# LINDIY.net
KiCad netlist of a schematic drawn in Altium Designer
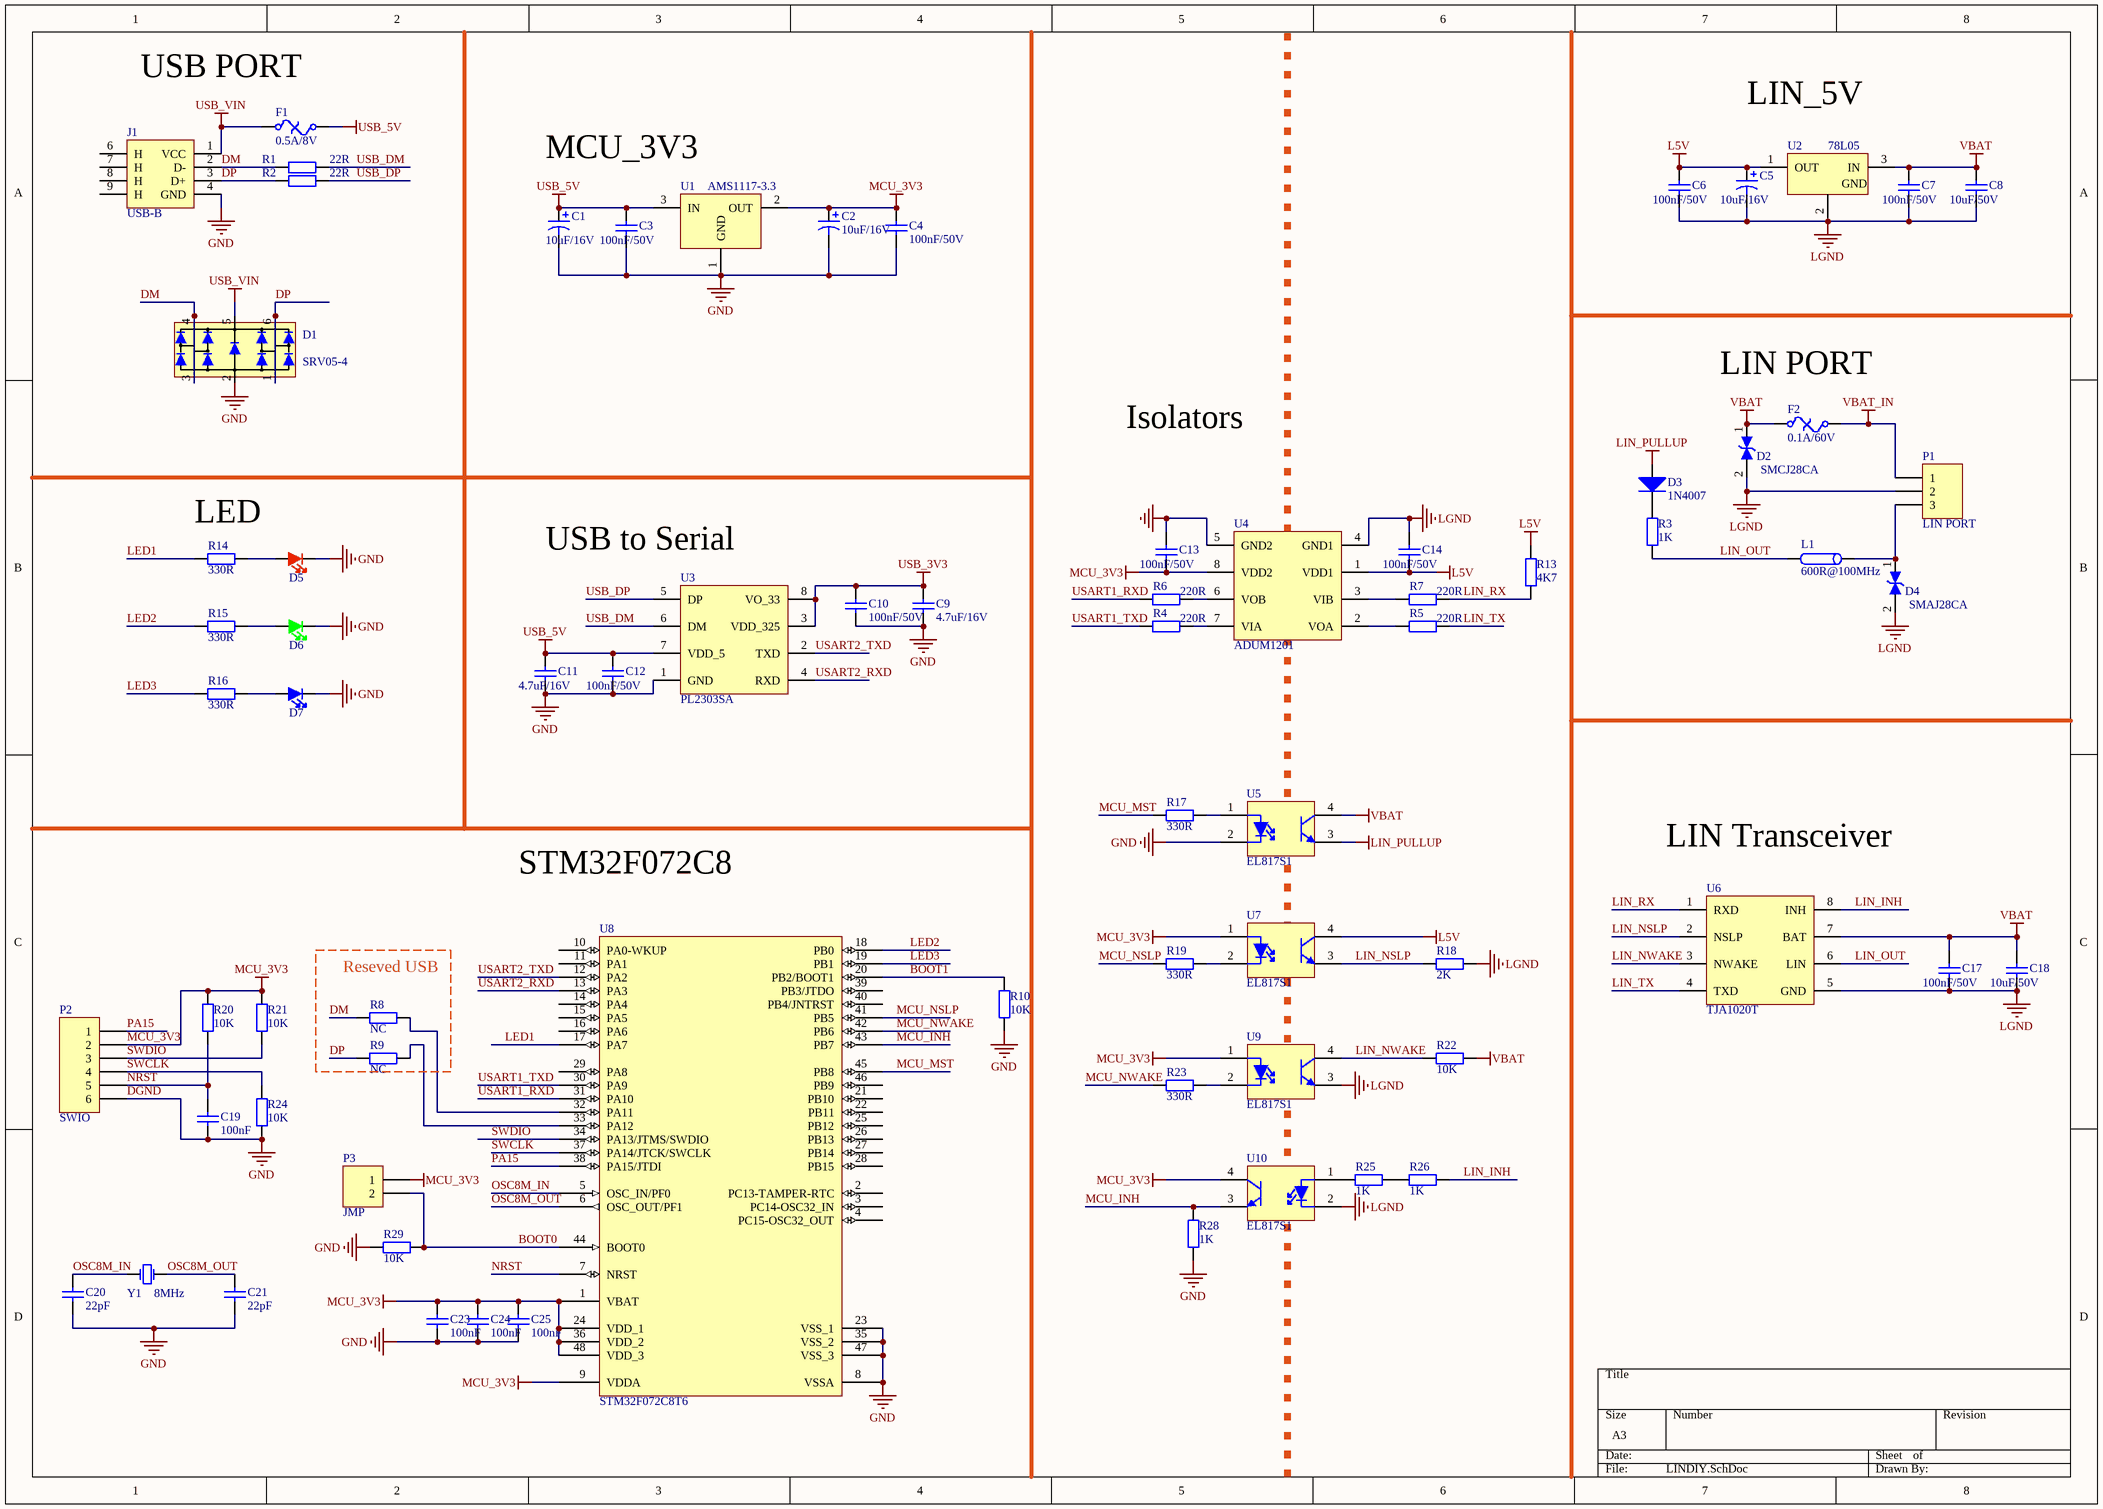
[diagram p0: LINDIY.SchDoc]

(export (version "E")
  (design (tool "Eeschema 10.0.6"))
  (components
    (comp (ref "C1")
      (value "10uF/16V")
      (footprint "LC-CASE-A_3216")
      (description "Polarized Capacitor (Axial)")
      (fields (field (name "PUBLISHER") "Altium Limited"))
      (libsource (lib "usrSchLib") (part "Cap Pol2"))
    )
    (comp (ref "C2")
      (value "10uF/16V")
      (footprint "LC-CASE-A_3216")
      (description "Polarized Capacitor (Axial)")
      (fields (field (name "PUBLISHER") "Altium Limited"))
      (libsource (lib "usrSchLib") (part "Cap Pol2"))
    )
    (comp (ref "C3")
      (value "100nF/50V")
      (footprint "LC-0603_C")
      (description "Capacitor")
      (fields (field (name "PUBLISHER") "Altium Limited"))
      (libsource (lib "usrSchLib") (part "Cap"))
    )
    (comp (ref "C4")
      (value "100nF/50V")
      (footprint "LC-0603_C")
      (description "Capacitor")
      (fields (field (name "PUBLISHER") "Altium Limited"))
      (libsource (lib "usrSchLib") (part "Cap"))
    )
    (comp (ref "C5")
      (value "10uF/16V")
      (footprint "LC-CASE-A_3216")
      (description "Polarized Capacitor (Axial)")
      (fields (field (name "PUBLISHER") "Altium Limited"))
      (libsource (lib "usrSchLib") (part "Cap Pol2"))
    )
    (comp (ref "C6")
      (value "100nF/50V")
      (footprint "LC-0603_C")
      (description "Capacitor")
      (fields (field (name "PUBLISHER") "Altium Limited"))
      (libsource (lib "usrSchLib") (part "Cap"))
    )
    (comp (ref "C7")
      (value "100nF/50V")
      (footprint "LC-0603_C")
      (description "Capacitor")
      (fields (field (name "PUBLISHER") "Altium Limited"))
      (libsource (lib "usrSchLib") (part "Cap"))
    )
    (comp (ref "C8")
      (value "10uF/50V")
      (footprint "LC-1206_C")
      (description "Capacitor")
      (fields (field (name "PUBLISHER") "Altium Limited"))
      (libsource (lib "usrSchLib") (part "Cap"))
    )
    (comp (ref "C9")
      (value "4.7uF/16V")
      (footprint "LC-0603_C")
      (description "Capacitor")
      (fields (field (name "PUBLISHER") "Altium Limited"))
      (libsource (lib "usrSchLib") (part "Cap"))
    )
    (comp (ref "C10")
      (value "100nF/50V")
      (footprint "LC-0603_C")
      (description "Capacitor")
      (fields (field (name "PUBLISHER") "Altium Limited"))
      (libsource (lib "usrSchLib") (part "Cap"))
    )
    (comp (ref "C11")
      (value "4.7uF/16V")
      (footprint "LC-0603_C")
      (description "Capacitor")
      (fields (field (name "PUBLISHER") "Altium Limited"))
      (libsource (lib "usrSchLib") (part "Cap"))
    )
    (comp (ref "C12")
      (value "100nF/50V")
      (footprint "LC-0603_C")
      (description "Capacitor")
      (fields (field (name "PUBLISHER") "Altium Limited"))
      (libsource (lib "usrSchLib") (part "Cap"))
    )
    (comp (ref "C13")
      (value "100nF/50V")
      (footprint "LC-0603_C")
      (description "Capacitor")
      (fields (field (name "PUBLISHER") "Altium Limited"))
      (libsource (lib "usrSchLib") (part "Cap"))
    )
    (comp (ref "C14")
      (value "100nF/50V")
      (footprint "LC-0603_C")
      (description "Capacitor")
      (fields (field (name "PUBLISHER") "Altium Limited"))
      (libsource (lib "usrSchLib") (part "Cap"))
    )
    (comp (ref "C17")
      (value "100nF/50V")
      (footprint "LC-0603_C")
      (description "Capacitor")
      (fields (field (name "PUBLISHER") "Altium Limited"))
      (libsource (lib "usrSchLib") (part "Cap"))
    )
    (comp (ref "C18")
      (value "10uF/50V")
      (footprint "LC-1206_C")
      (description "Capacitor")
      (fields (field (name "PUBLISHER") "Altium Limited"))
      (libsource (lib "usrSchLib") (part "Cap"))
    )
    (comp (ref "C19")
      (value "100nF")
      (footprint "LC-0603_C")
      (description "Capacitor")
      (fields (field (name "PUBLISHER") "Altium Limited"))
      (libsource (lib "usrSchLib") (part "Cap"))
    )
    (comp (ref "C20")
      (value "22pF")
      (footprint "LC-0603_C")
      (description "Capacitor")
      (fields (field (name "PUBLISHER") "Altium Limited"))
      (libsource (lib "usrSchLib") (part "Cap"))
    )
    (comp (ref "C21")
      (value "22pF")
      (footprint "LC-0603_C")
      (description "Capacitor")
      (fields (field (name "PUBLISHER") "Altium Limited"))
      (libsource (lib "usrSchLib") (part "Cap"))
    )
    (comp (ref "C23")
      (value "100nF")
      (footprint "LC-0603_C")
      (description "Capacitor")
      (fields (field (name "PUBLISHER") "Altium Limited"))
      (libsource (lib "usrSchLib") (part "Cap"))
    )
    (comp (ref "C24")
      (value "100nF")
      (footprint "LC-0603_C")
      (description "Capacitor")
      (fields (field (name "PUBLISHER") "Altium Limited"))
      (libsource (lib "usrSchLib") (part "Cap"))
    )
    (comp (ref "C25")
      (value "100nF")
      (footprint "LC-0603_C")
      (description "Capacitor")
      (fields (field (name "PUBLISHER") "Altium Limited"))
      (libsource (lib "usrSchLib") (part "Cap"))
    )
    (comp (ref "D1")
      (value "SRV05-4")
      (footprint "LC-SOT-23-6")
      (description "Low Capacitance TVS Diode Array")
      (libsource (lib "usrSchLib") (part "SRV05-4"))
    )
    (comp (ref "D2")
      (value "SMCJ28CA")
      (footprint "LC-SMC(DO-214AB)_S1")
      (description "Zener Diode")
      (libsource (lib "usrSchLib") (part "P6KE6.8CA"))
    )
    (comp (ref "D3")
      (value "1N4007")
      (footprint "LC-SMA(DO-214AC)_S1")
      (description "Silicon Low Leakage Diode")
      (fields (field (name "PUBLISHER") "Altium Limited"))
      (libsource (lib "usrSchLib") (part "Diode BAS116"))
    )
    (comp (ref "D4")
      (value "SMAJ28CA")
      (footprint "LC-SMA(DO-214AC)_S1")
      (description "Zener Diode")
      (libsource (lib "usrSchLib") (part "P6KE6.8CA"))
    )
    (comp (ref "D5")
      (value "LED_RED")
      (footprint "LC-0805_LED_S1")
      (libsource (lib "usrSchLib") (part "LED-R"))
    )
    (comp (ref "D6")
      (value "LED_GREEG")
      (footprint "LC-0805_LED_S1")
      (libsource (lib "usrSchLib") (part "LED-G"))
    )
    (comp (ref "D7")
      (value "LED_RED")
      (footprint "LC-0805_LED_S1")
      (libsource (lib "usrSchLib") (part "LED-B"))
    )
    (comp (ref "F1")
      (value "0.5A/8V")
      (footprint "LC-1206_R")
      (description "Thermal Fuse")
      (fields (field (name "PUBLISHER") "Altium Limited"))
      (libsource (lib "usrSchLib") (part "Fuse Thermal"))
    )
    (comp (ref "F2")
      (value "0.1A/60V")
      (footprint "LC-1206_R")
      (description "Thermal Fuse")
      (fields (field (name "PUBLISHER") "Altium Limited"))
      (libsource (lib "usrSchLib") (part "Fuse Thermal"))
    )
    (comp (ref "J1") (value "USB-B") (footprint "USB/B") (libsource (lib "usrSchLib") (part "MINI-USB")))
    (comp (ref "L1")
      (value "600R@100MHz")
      (footprint "LC-1206_L")
      (libsource (lib "usrSchLib") (part "FerriteBeads"))
    )
    (comp (ref "P1")
      (value "LIN PORT")
      (footprint "5.08-3")
      (description "Header, 3-Pin")
      (fields (field (name "PUBLISHER") "Altium Limited"))
      (libsource (lib "Miscellaneous Connectors") (part "Header 3"))
    )
    (comp (ref "P2")
      (value "SWIO")
      (footprint "HDR1X6")
      (description "Header, 6-Pin")
      (fields (field (name "PUBLISHER") "Altium Limited"))
      (libsource (lib "Miscellaneous Connectors") (part "Header 6"))
    )
    (comp (ref "P3")
      (value "JMP")
      (footprint "HDR1X2")
      (description "Header, 2-Pin")
      (fields (field (name "PUBLISHER") "Altium Limited"))
      (libsource (lib "Miscellaneous Connectors") (part "Header 2"))
    )
    (comp (ref "R1")
      (value "22R")
      (footprint "LC-0603_R")
      (description "Resistor")
      (fields (field (name "PUBLISHER") "Altium Limited"))
      (libsource (lib "usrSchLib") (part "Res2"))
    )
    (comp (ref "R2")
      (value "22R")
      (footprint "LC-0603_R")
      (description "Resistor")
      (fields (field (name "PUBLISHER") "Altium Limited"))
      (libsource (lib "usrSchLib") (part "Res2"))
    )
    (comp (ref "R3")
      (value "1K")
      (footprint "LC-1206_R")
      (description "Resistor")
      (fields (field (name "PUBLISHER") "Altium Limited"))
      (libsource (lib "") (part "Res2_3"))
    )
    (comp (ref "R4")
      (value "220R")
      (footprint "LC-0603_R")
      (description "Resistor")
      (fields (field (name "PUBLISHER") "Altium Limited"))
      (libsource (lib "usrSchLib") (part "Res2"))
    )
    (comp (ref "R5")
      (value "220R")
      (footprint "LC-0603_R")
      (description "Resistor")
      (fields (field (name "PUBLISHER") "Altium Limited"))
      (libsource (lib "usrSchLib") (part "Res2"))
    )
    (comp (ref "R6")
      (value "220R")
      (footprint "LC-0603_R")
      (description "Resistor")
      (fields (field (name "PUBLISHER") "Altium Limited"))
      (libsource (lib "usrSchLib") (part "Res2"))
    )
    (comp (ref "R7")
      (value "220R")
      (footprint "LC-0603_R")
      (description "Resistor")
      (fields (field (name "PUBLISHER") "Altium Limited"))
      (libsource (lib "usrSchLib") (part "Res2"))
    )
    (comp (ref "R8")
      (value "NC")
      (footprint "LC-0603_R")
      (description "Resistor")
      (fields (field (name "PUBLISHER") "Altium Limited"))
      (libsource (lib "usrSchLib") (part "Res2"))
    )
    (comp (ref "R9")
      (value "NC")
      (footprint "LC-0603_R")
      (description "Resistor")
      (fields (field (name "PUBLISHER") "Altium Limited"))
      (libsource (lib "usrSchLib") (part "Res2"))
    )
    (comp (ref "R10")
      (value "10K")
      (footprint "LC-0603_R")
      (description "Resistor")
      (fields (field (name "PUBLISHER") "Altium Limited"))
      (libsource (lib "") (part "Res2_3"))
    )
    (comp (ref "R13")
      (value "4K7")
      (footprint "LC-0603_R")
      (description "Resistor")
      (fields (field (name "PUBLISHER") "Altium Limited"))
      (libsource (lib "") (part "Res2_3"))
    )
    (comp (ref "R14")
      (value "330R")
      (footprint "LC-0603_R")
      (description "Resistor")
      (fields (field (name "PUBLISHER") "Altium Limited"))
      (libsource (lib "usrSchLib") (part "Res2"))
    )
    (comp (ref "R15")
      (value "330R")
      (footprint "LC-0603_R")
      (description "Resistor")
      (fields (field (name "PUBLISHER") "Altium Limited"))
      (libsource (lib "usrSchLib") (part "Res2"))
    )
    (comp (ref "R16")
      (value "330R")
      (footprint "LC-0603_R")
      (description "Resistor")
      (fields (field (name "PUBLISHER") "Altium Limited"))
      (libsource (lib "usrSchLib") (part "Res2"))
    )
    (comp (ref "R17")
      (value "330R")
      (footprint "LC-0603_R")
      (description "Resistor")
      (fields (field (name "PUBLISHER") "Altium Limited"))
      (libsource (lib "usrSchLib") (part "Res2"))
    )
    (comp (ref "R18")
      (value "2K")
      (footprint "LC-0603_R")
      (description "Resistor")
      (fields (field (name "PUBLISHER") "Altium Limited"))
      (libsource (lib "") (part "Res2_2"))
    )
    (comp (ref "R19")
      (value "330R")
      (footprint "LC-0603_R")
      (description "Resistor")
      (fields (field (name "PUBLISHER") "Altium Limited"))
      (libsource (lib "usrSchLib") (part "Res2"))
    )
    (comp (ref "R20")
      (value "10K")
      (footprint "LC-0603_R")
      (description "Resistor")
      (fields (field (name "PUBLISHER") "Altium Limited"))
      (libsource (lib "") (part "Res2_1"))
    )
    (comp (ref "R21")
      (value "10K")
      (footprint "LC-0603_R")
      (description "Resistor")
      (fields (field (name "PUBLISHER") "Altium Limited"))
      (libsource (lib "") (part "Res2_1"))
    )
    (comp (ref "R22")
      (value "10K")
      (footprint "LC-0603_R")
      (description "Resistor")
      (fields (field (name "PUBLISHER") "Altium Limited"))
      (libsource (lib "") (part "Res2_2"))
    )
    (comp (ref "R23")
      (value "330R")
      (footprint "LC-0603_R")
      (description "Resistor")
      (fields (field (name "PUBLISHER") "Altium Limited"))
      (libsource (lib "usrSchLib") (part "Res2"))
    )
    (comp (ref "R24")
      (value "10K")
      (footprint "LC-0603_R")
      (description "Resistor")
      (fields (field (name "PUBLISHER") "Altium Limited"))
      (libsource (lib "") (part "Res2_1"))
    )
    (comp (ref "R25")
      (value "1K")
      (footprint "LC-1206_R")
      (description "Resistor")
      (fields (field (name "PUBLISHER") "Altium Limited"))
      (libsource (lib "") (part "Res2_2"))
    )
    (comp (ref "R26")
      (value "1K")
      (footprint "LC-1206_R")
      (description "Resistor")
      (fields (field (name "PUBLISHER") "Altium Limited"))
      (libsource (lib "") (part "Res2_2"))
    )
    (comp (ref "R28")
      (value "1K")
      (footprint "LC-0603_R")
      (description "Resistor")
      (fields (field (name "PUBLISHER") "Altium Limited"))
      (libsource (lib "") (part "Res2_3"))
    )
    (comp (ref "R29")
      (value "10K")
      (footprint "LC-0603_R")
      (description "Resistor")
      (fields (field (name "PUBLISHER") "Altium Limited"))
      (libsource (lib "usrSchLib") (part "Res2"))
    )
    (comp (ref "U1")
      (value "AMS1117-3.3")
      (footprint "LC-SOT-223")
      (libsource (lib "usrSchLib") (part "AMS1117"))
    )
    (comp (ref "U2")
      (value "78L05")
      (footprint "LC-SOT-89(SOT-89-3)")
      (description "Three-Terminal Positive Voltage Regulator")
      (fields (field (name "PUBLISHER") "Altium Limited"))
      (libsource (lib "usrSchLib") (part "MC7805ACT"))
    )
    (comp (ref "U3")
      (value "PL2303SA")
      (footprint "LC-SO-8_3.9mm")
      (description "USB to Serial Bridge Controller (SOP8 Package)")
      (libsource (lib "usrSchLib") (part "PL2303SA"))
    )
    (comp (ref "U4")
      (value "ADUM1201")
      (footprint "LC-SO-8_3.9mm")
      (description "Dual-Channel Digital Isolators")
      (libsource (lib "usrSchLib") (part "ADUM1201"))
    )
    (comp (ref "U5") (value "EL817S1") (footprint "LC-SMD-4") (libsource (lib "usrSchLib") (part "TLP521-1")))
    (comp (ref "U6")
      (value "TJA1020T")
      (footprint "LC-SOIC-8_150mil")
      (description "LIN transceiver")
      (libsource (lib "usrSchLib") (part "TJA1020"))
    )
    (comp (ref "U7") (value "EL817S1") (footprint "LC-SMD-4") (libsource (lib "usrSchLib") (part "TLP521-1")))
    (comp (ref "U8")
      (value "STM32F072C8T6")
      (footprint "LC-LQFP-48_7x7x05P")
      (description "STM32 ARM-based 32-bit MCU with 64 Kbytes Flash, 48-pin LQFP, Industrial Temperature")
      (fields (field (name "PUBLISHER") "Altium Limited"))
      (libsource (lib "ST Microcontroller 32-Bit STM32") (part "STM32F103C8T6"))
    )
    (comp (ref "U9") (value "EL817S1") (footprint "LC-SMD-4") (libsource (lib "usrSchLib") (part "TLP521-1")))
    (comp (ref "U10") (value "EL817S1") (footprint "LC-SMD-4") (libsource (lib "") (part "TLP521-1_1")))
    (comp (ref "Y1")
      (value "8MHz")
      (footprint "LC-SMD-3225_4P")
      (description "Crystal Oscillator")
      (fields (field (name "PUBLISHER") "Altium Limited"))
      (libsource (lib "usrSchLib") (part "XTAL"))
    )
  )
  (nets
    (net (code "1") (name "/BOOT0") (class "Default")
      (node (ref "P3") (pin "2") (pinfunction "2_2") (pintype "passive"))
      (node (ref "R29") (pin "2") (pinfunction "2_2") (pintype "passive"))
      (node (ref "U8") (pin "44") (pinfunction "BOOT0_44") (pintype "input"))
    )
    (net (code "2") (name "/BOOT1") (class "Default")
      (node (ref "R10") (pin "2") (pinfunction "2_2") (pintype "passive"))
      (node (ref "U8") (pin "20") (pinfunction "PB2/BOOT1_20") (pintype "bidirectional"))
    )
    (net (code "3") (name "/DM") (class "Default")
      (node (ref "D1") (pin "3") (pinfunction "3_3") (pintype "passive"))
      (node (ref "D1") (pin "4") (pinfunction "4_4") (pintype "passive"))
      (node (ref "J1") (pin "2") (pinfunction "D-_2") (pintype "passive"))
      (node (ref "R1") (pin "1") (pinfunction "1_1") (pintype "passive"))
      (node (ref "R8") (pin "1") (pinfunction "1_1") (pintype "passive"))
    )
    (net (code "4") (name "/DP") (class "Default")
      (node (ref "D1") (pin "1") (pinfunction "1_1") (pintype "passive"))
      (node (ref "D1") (pin "6") (pinfunction "6_6") (pintype "passive"))
      (node (ref "J1") (pin "3") (pinfunction "D+_3") (pintype "passive"))
      (node (ref "R2") (pin "1") (pinfunction "1_1") (pintype "passive"))
      (node (ref "R9") (pin "1") (pinfunction "1_1") (pintype "passive"))
    )
    (net (code "5") (name "/LED1") (class "Default")
      (node (ref "R14") (pin "1") (pinfunction "1_1") (pintype "passive"))
      (node (ref "U8") (pin "17") (pinfunction "PA7_17") (pintype "bidirectional"))
    )
    (net (code "6") (name "/LED2") (class "Default")
      (node (ref "R15") (pin "1") (pinfunction "1_1") (pintype "passive"))
      (node (ref "U8") (pin "18") (pinfunction "PB0_18") (pintype "bidirectional"))
    )
    (net (code "7") (name "/LED3") (class "Default")
      (node (ref "R16") (pin "1") (pinfunction "1_1") (pintype "passive"))
      (node (ref "U8") (pin "19") (pinfunction "PB1_19") (pintype "bidirectional"))
    )
    (net (code "8") (name "/LIN_INH") (class "Default")
      (node (ref "R26") (pin "1") (pinfunction "1_1") (pintype "passive"))
      (node (ref "U6") (pin "8") (pinfunction "INH_8") (pintype "passive"))
    )
    (net (code "9") (name "/LIN_NSLP") (class "Default")
      (node (ref "R18") (pin "2") (pinfunction "2_2") (pintype "passive"))
      (node (ref "U6") (pin "2") (pinfunction "NSLP_2") (pintype "passive"))
      (node (ref "U7") (pin "3") (pinfunction "3_3") (pintype "passive"))
    )
    (net (code "10") (name "/LIN_NWAKE") (class "Default")
      (node (ref "R22") (pin "2") (pinfunction "2_2") (pintype "passive"))
      (node (ref "U6") (pin "3") (pinfunction "NWAKE_3") (pintype "passive"))
      (node (ref "U9") (pin "4") (pinfunction "4_4") (pintype "passive"))
    )
    (net (code "11") (name "/LIN_OUT") (class "Default")
      (node (ref "L1") (pin "2") (pinfunction "2_2") (pintype "passive"))
      (node (ref "R3") (pin "1") (pinfunction "1_1") (pintype "passive"))
      (node (ref "U6") (pin "6") (pinfunction "LIN_6") (pintype "passive"))
    )
    (net (code "12") (name "/LIN_RX") (class "Default")
      (node (ref "R13") (pin "1") (pinfunction "1_1") (pintype "passive"))
      (node (ref "R7") (pin "2") (pinfunction "2_2") (pintype "passive"))
      (node (ref "U6") (pin "1") (pinfunction "RXD_1") (pintype "passive"))
    )
    (net (code "13") (name "/LIN_TX") (class "Default")
      (node (ref "R5") (pin "2") (pinfunction "2_2") (pintype "passive"))
      (node (ref "U6") (pin "4") (pinfunction "TXD_4") (pintype "passive"))
    )
    (net (code "14") (name "/MCU_INH") (class "Default")
      (node (ref "R28") (pin "2") (pinfunction "2_2") (pintype "passive"))
      (node (ref "U10") (pin "3") (pinfunction "3_3") (pintype "passive"))
      (node (ref "U8") (pin "43") (pinfunction "PB7_43") (pintype "bidirectional"))
    )
    (net (code "15") (name "/MCU_MST") (class "Default")
      (node (ref "R17") (pin "1") (pinfunction "1_1") (pintype "passive"))
      (node (ref "U8") (pin "45") (pinfunction "PB8_45") (pintype "bidirectional"))
    )
    (net (code "16") (name "/MCU_NSLP") (class "Default")
      (node (ref "R19") (pin "1") (pinfunction "1_1") (pintype "passive"))
      (node (ref "U8") (pin "41") (pinfunction "PB5_41") (pintype "bidirectional"))
    )
    (net (code "17") (name "/MCU_NWAKE") (class "Default")
      (node (ref "R23") (pin "1") (pinfunction "1_1") (pintype "passive"))
      (node (ref "U8") (pin "42") (pinfunction "PB6_42") (pintype "bidirectional"))
    )
    (net (code "18") (name "/NRST") (class "Default")
      (node (ref "C19") (pin "1") (pinfunction "1_1") (pintype "passive"))
      (node (ref "P2") (pin "5") (pinfunction "5_5") (pintype "passive"))
      (node (ref "R20") (pin "2") (pinfunction "2_2") (pintype "passive"))
      (node (ref "U8") (pin "7") (pinfunction "NRST_7") (pintype "bidirectional"))
    )
    (net (code "19") (name "/OSC8M_IN") (class "Default")
      (node (ref "C20") (pin "1") (pinfunction "1_1") (pintype "passive"))
      (node (ref "U8") (pin "5") (pinfunction "OSC_IN/PF0_5") (pintype "input"))
      (node (ref "Y1") (pin "3") (pinfunction "OSC2_3") (pintype "passive"))
    )
    (net (code "20") (name "/OSC8M_OUT") (class "Default")
      (node (ref "C21") (pin "1") (pinfunction "1_1") (pintype "passive"))
      (node (ref "U8") (pin "6") (pinfunction "OSC_OUT/PF1_6") (pintype "output"))
      (node (ref "Y1") (pin "1") (pinfunction "OSC1_1") (pintype "passive"))
    )
    (net (code "21") (name "/PA15") (class "Default")
      (node (ref "P2") (pin "1") (pinfunction "1_1") (pintype "passive"))
      (node (ref "U8") (pin "38") (pinfunction "PA15/JTDI_38") (pintype "bidirectional"))
    )
    (net (code "22") (name "/SWCLK") (class "Default")
      (node (ref "P2") (pin "4") (pinfunction "4_4") (pintype "passive"))
      (node (ref "R24") (pin "1") (pinfunction "1_1") (pintype "passive"))
      (node (ref "U8") (pin "37") (pinfunction "PA14/JTCK/SWCLK_37") (pintype "bidirectional"))
    )
    (net (code "23") (name "/SWDIO") (class "Default")
      (node (ref "P2") (pin "3") (pinfunction "3_3") (pintype "passive"))
      (node (ref "R21") (pin "2") (pinfunction "2_2") (pintype "passive"))
      (node (ref "U8") (pin "34") (pinfunction "PA13/JTMS/SWDIO_34") (pintype "bidirectional"))
    )
    (net (code "24") (name "/USART1_RXD") (class "Default")
      (node (ref "R6") (pin "1") (pinfunction "1_1") (pintype "passive"))
      (node (ref "U8") (pin "31") (pinfunction "PA10_31") (pintype "bidirectional"))
    )
    (net (code "25") (name "/USART1_TXD") (class "Default")
      (node (ref "R4") (pin "1") (pinfunction "1_1") (pintype "passive"))
      (node (ref "U8") (pin "30") (pinfunction "PA9_30") (pintype "bidirectional"))
    )
    (net (code "26") (name "/USART2_RXD") (class "Default")
      (node (ref "U3") (pin "4") (pinfunction "RXD_4") (pintype "passive"))
      (node (ref "U8") (pin "13") (pinfunction "PA3_13") (pintype "bidirectional"))
    )
    (net (code "27") (name "/USART2_TXD") (class "Default")
      (node (ref "U3") (pin "2") (pinfunction "TXD_2") (pintype "passive"))
      (node (ref "U8") (pin "12") (pinfunction "PA2_12") (pintype "bidirectional"))
    )
    (net (code "28") (name "/USB_DM") (class "Default")
      (node (ref "R1") (pin "2") (pinfunction "2_2") (pintype "passive"))
      (node (ref "U3") (pin "6") (pinfunction "DM_6") (pintype "passive"))
    )
    (net (code "29") (name "/USB_DP") (class "Default")
      (node (ref "R2") (pin "2") (pinfunction "2_2") (pintype "passive"))
      (node (ref "U3") (pin "5") (pinfunction "DP_5") (pintype "passive"))
    )
    (net (code "30") (name "GND") (class "Default")
      (node (ref "C1") (pin "2") (pinfunction "2_2") (pintype "passive"))
      (node (ref "C10") (pin "2") (pinfunction "2_2") (pintype "passive"))
      (node (ref "C11") (pin "2") (pinfunction "2_2") (pintype "passive"))
      (node (ref "C12") (pin "2") (pinfunction "2_2") (pintype "passive"))
      (node (ref "C13") (pin "1") (pinfunction "1_1") (pintype "passive"))
      (node (ref "C19") (pin "2") (pinfunction "2_2") (pintype "passive"))
      (node (ref "C2") (pin "2") (pinfunction "2_2") (pintype "passive"))
      (node (ref "C20") (pin "2") (pinfunction "2_2") (pintype "passive"))
      (node (ref "C21") (pin "2") (pinfunction "2_2") (pintype "passive"))
      (node (ref "C23") (pin "2") (pinfunction "2_2") (pintype "passive"))
      (node (ref "C24") (pin "2") (pinfunction "2_2") (pintype "passive"))
      (node (ref "C25") (pin "2") (pinfunction "2_2") (pintype "passive"))
      (node (ref "C3") (pin "2") (pinfunction "2_2") (pintype "passive"))
      (node (ref "C4") (pin "2") (pinfunction "2_2") (pintype "passive"))
      (node (ref "C9") (pin "2") (pinfunction "2_2") (pintype "passive"))
      (node (ref "D1") (pin "2") (pinfunction "2_2") (pintype "passive"))
      (node (ref "D5") (pin "K") (pinfunction "k_K") (pintype "passive"))
      (node (ref "D6") (pin "K") (pinfunction "k_K") (pintype "passive"))
      (node (ref "D7") (pin "K") (pinfunction "k_K") (pintype "passive"))
      (node (ref "J1") (pin "4") (pinfunction "GND_4") (pintype "passive"))
      (node (ref "P2") (pin "6") (pinfunction "6_6") (pintype "passive"))
      (node (ref "R10") (pin "1") (pinfunction "1_1") (pintype "passive"))
      (node (ref "R24") (pin "2") (pinfunction "2_2") (pintype "passive"))
      (node (ref "R28") (pin "1") (pinfunction "1_1") (pintype "passive"))
      (node (ref "R29") (pin "1") (pinfunction "1_1") (pintype "passive"))
      (node (ref "U1") (pin "1") (pinfunction "GND_1") (pintype "passive"))
      (node (ref "U3") (pin "1") (pinfunction "GND_1") (pintype "passive"))
      (node (ref "U4") (pin "5") (pinfunction "GND2_5") (pintype "passive"))
      (node (ref "U5") (pin "2") (pinfunction "2_2") (pintype "passive"))
      (node (ref "U8") (pin "23") (pinfunction "VSS_1_23") (pintype "power_in"))
      (node (ref "U8") (pin "35") (pinfunction "VSS_2_35") (pintype "power_in"))
      (node (ref "U8") (pin "47") (pinfunction "VSS_3_47") (pintype "power_in"))
      (node (ref "U8") (pin "8") (pinfunction "VSSA_8") (pintype "power_in"))
    )
    (net (code "31") (name "L5V") (class "Default")
      (node (ref "C14") (pin "2") (pinfunction "2_2") (pintype "passive"))
      (node (ref "C5") (pin "1") (pinfunction "1_1") (pintype "passive"))
      (node (ref "C6") (pin "1") (pinfunction "1_1") (pintype "passive"))
      (node (ref "R13") (pin "2") (pinfunction "2_2") (pintype "passive"))
      (node (ref "U2") (pin "1") (pinfunction "OUT_1") (pintype "power_in"))
      (node (ref "U4") (pin "1") (pinfunction "VDD1_1") (pintype "passive"))
      (node (ref "U7") (pin "4") (pinfunction "4_4") (pintype "passive"))
    )
    (net (code "32") (name "LGND") (class "Default")
      (node (ref "C14") (pin "1") (pinfunction "1_1") (pintype "passive"))
      (node (ref "C17") (pin "2") (pinfunction "2_2") (pintype "passive"))
      (node (ref "C18") (pin "2") (pinfunction "2_2") (pintype "passive"))
      (node (ref "C5") (pin "2") (pinfunction "2_2") (pintype "passive"))
      (node (ref "C6") (pin "2") (pinfunction "2_2") (pintype "passive"))
      (node (ref "C7") (pin "2") (pinfunction "2_2") (pintype "passive"))
      (node (ref "C8") (pin "2") (pinfunction "2_2") (pintype "passive"))
      (node (ref "D2") (pin "2") (pinfunction "2_2") (pintype "passive"))
      (node (ref "D4") (pin "2") (pinfunction "2_2") (pintype "passive"))
      (node (ref "P1") (pin "2") (pinfunction "2_2") (pintype "passive"))
      (node (ref "R18") (pin "1") (pinfunction "1_1") (pintype "passive"))
      (node (ref "U10") (pin "2") (pinfunction "2_2") (pintype "passive"))
      (node (ref "U2") (pin "2") (pinfunction "GND_2") (pintype "power_in"))
      (node (ref "U4") (pin "4") (pinfunction "GND1_4") (pintype "passive"))
      (node (ref "U6") (pin "5") (pinfunction "GND_5") (pintype "passive"))
      (node (ref "U9") (pin "3") (pinfunction "3_3") (pintype "passive"))
    )
    (net (code "33") (name "LIN_PULLUP") (class "Default")
      (node (ref "D3") (pin "1") (pinfunction "A_1") (pintype "passive"))
      (node (ref "U5") (pin "3") (pinfunction "3_3") (pintype "passive"))
    )
    (net (code "34") (name "MCU_3V3") (class "Default")
      (node (ref "C13") (pin "2") (pinfunction "2_2") (pintype "passive"))
      (node (ref "C2") (pin "1") (pinfunction "1_1") (pintype "passive"))
      (node (ref "C23") (pin "1") (pinfunction "1_1") (pintype "passive"))
      (node (ref "C24") (pin "1") (pinfunction "1_1") (pintype "passive"))
      (node (ref "C25") (pin "1") (pinfunction "1_1") (pintype "passive"))
      (node (ref "C4") (pin "1") (pinfunction "1_1") (pintype "passive"))
      (node (ref "P2") (pin "2") (pinfunction "2_2") (pintype "passive"))
      (node (ref "P3") (pin "1") (pinfunction "1_1") (pintype "passive"))
      (node (ref "R20") (pin "1") (pinfunction "1_1") (pintype "passive"))
      (node (ref "R21") (pin "1") (pinfunction "1_1") (pintype "passive"))
      (node (ref "U1") (pin "2") (pinfunction "OUT_2") (pintype "passive"))
      (node (ref "U10") (pin "4") (pinfunction "4_4") (pintype "passive"))
      (node (ref "U4") (pin "8") (pinfunction "VDD2_8") (pintype "passive"))
      (node (ref "U7") (pin "1") (pinfunction "1_1") (pintype "passive"))
      (node (ref "U8") (pin "1") (pinfunction "VBAT_1") (pintype "power_in"))
      (node (ref "U8") (pin "24") (pinfunction "VDD_1_24") (pintype "power_in"))
      (node (ref "U8") (pin "36") (pinfunction "VDD_2_36") (pintype "power_in"))
      (node (ref "U8") (pin "48") (pinfunction "VDD_3_48") (pintype "power_in"))
      (node (ref "U8") (pin "9") (pinfunction "VDDA_9") (pintype "power_in"))
      (node (ref "U9") (pin "1") (pinfunction "1_1") (pintype "passive"))
    )
    (net (code "35") (name "Net-(D3-K)") (class "Default")
      (node (ref "D3") (pin "2") (pinfunction "K_2") (pintype "passive"))
      (node (ref "R3") (pin "2") (pinfunction "2_2") (pintype "passive"))
    )
    (net (code "36") (name "Net-(D4-Pad1)") (class "Default")
      (node (ref "D4") (pin "1") (pinfunction "1_1") (pintype "passive"))
      (node (ref "L1") (pin "1") (pinfunction "1_1") (pintype "passive"))
      (node (ref "P1") (pin "3") (pinfunction "3_3") (pintype "passive"))
    )
    (net (code "37") (name "Net-(D5-a)") (class "Default")
      (node (ref "D5") (pin "A") (pinfunction "a_A") (pintype "passive"))
      (node (ref "R14") (pin "2") (pinfunction "2_2") (pintype "passive"))
    )
    (net (code "38") (name "Net-(D6-a)") (class "Default")
      (node (ref "D6") (pin "A") (pinfunction "a_A") (pintype "passive"))
      (node (ref "R15") (pin "2") (pinfunction "2_2") (pintype "passive"))
    )
    (net (code "39") (name "Net-(D7-a)") (class "Default")
      (node (ref "D7") (pin "A") (pinfunction "a_A") (pintype "passive"))
      (node (ref "R16") (pin "2") (pinfunction "2_2") (pintype "passive"))
    )
    (net (code "40") (name "Net-(R17-Pad2)") (class "Default")
      (node (ref "R17") (pin "2") (pinfunction "2_2") (pintype "passive"))
      (node (ref "U5") (pin "1") (pinfunction "1_1") (pintype "passive"))
    )
    (net (code "41") (name "Net-(R19-Pad2)") (class "Default")
      (node (ref "R19") (pin "2") (pinfunction "2_2") (pintype "passive"))
      (node (ref "U7") (pin "2") (pinfunction "2_2") (pintype "passive"))
    )
    (net (code "42") (name "Net-(R23-Pad2)") (class "Default")
      (node (ref "R23") (pin "2") (pinfunction "2_2") (pintype "passive"))
      (node (ref "U9") (pin "2") (pinfunction "2_2") (pintype "passive"))
    )
    (net (code "43") (name "Net-(R25-Pad1)") (class "Default")
      (node (ref "R25") (pin "1") (pinfunction "1_1") (pintype "passive"))
      (node (ref "R26") (pin "2") (pinfunction "2_2") (pintype "passive"))
    )
    (net (code "44") (name "Net-(R25-Pad2)") (class "Default")
      (node (ref "R25") (pin "2") (pinfunction "2_2") (pintype "passive"))
      (node (ref "U10") (pin "1") (pinfunction "1_1") (pintype "passive"))
    )
    (net (code "45") (name "Net-(U4-VIA)") (class "Default")
      (node (ref "R4") (pin "2") (pinfunction "2_2") (pintype "passive"))
      (node (ref "U4") (pin "7") (pinfunction "VIA_7") (pintype "passive"))
    )
    (net (code "46") (name "Net-(U4-VIB)") (class "Default")
      (node (ref "R7") (pin "1") (pinfunction "1_1") (pintype "passive"))
      (node (ref "U4") (pin "3") (pinfunction "VIB_3") (pintype "passive"))
    )
    (net (code "47") (name "Net-(U4-VOA)") (class "Default")
      (node (ref "R5") (pin "1") (pinfunction "1_1") (pintype "passive"))
      (node (ref "U4") (pin "2") (pinfunction "VOA_2") (pintype "passive"))
    )
    (net (code "48") (name "Net-(U4-VOB)") (class "Default")
      (node (ref "R6") (pin "2") (pinfunction "2_2") (pintype "passive"))
      (node (ref "U4") (pin "6") (pinfunction "VOB_6") (pintype "passive"))
    )
    (net (code "49") (name "Net-(U8-PA11)") (class "Default")
      (node (ref "R8") (pin "2") (pinfunction "2_2") (pintype "passive"))
      (node (ref "U8") (pin "32") (pinfunction "PA11_32") (pintype "bidirectional"))
    )
    (net (code "50") (name "Net-(U8-PA12)") (class "Default")
      (node (ref "R9") (pin "2") (pinfunction "2_2") (pintype "passive"))
      (node (ref "U8") (pin "33") (pinfunction "PA12_33") (pintype "bidirectional"))
    )
    (net (code "51") (name "USB_3V3") (class "Default")
      (node (ref "C10") (pin "1") (pinfunction "1_1") (pintype "passive"))
      (node (ref "C9") (pin "1") (pinfunction "1_1") (pintype "passive"))
      (node (ref "U3") (pin "3") (pinfunction "VDD_325_3") (pintype "passive"))
      (node (ref "U3") (pin "8") (pinfunction "VO_33_8") (pintype "passive"))
    )
    (net (code "52") (name "USB_5V") (class "Default")
      (node (ref "C1") (pin "1") (pinfunction "1_1") (pintype "passive"))
      (node (ref "C11") (pin "1") (pinfunction "1_1") (pintype "passive"))
      (node (ref "C12") (pin "1") (pinfunction "1_1") (pintype "passive"))
      (node (ref "C3") (pin "1") (pinfunction "1_1") (pintype "passive"))
      (node (ref "F1") (pin "2") (pinfunction "2_2") (pintype "passive"))
      (node (ref "U1") (pin "3") (pinfunction "IN_3") (pintype "passive"))
      (node (ref "U3") (pin "7") (pinfunction "VDD_5_7") (pintype "passive"))
    )
    (net (code "53") (name "USB_VIN") (class "Default")
      (node (ref "D1") (pin "5") (pinfunction "5_5") (pintype "passive"))
      (node (ref "F1") (pin "1") (pinfunction "1_1") (pintype "passive"))
      (node (ref "J1") (pin "1") (pinfunction "VCC_1") (pintype "passive"))
    )
    (net (code "54") (name "VBAT") (class "Default")
      (node (ref "C17") (pin "1") (pinfunction "1_1") (pintype "passive"))
      (node (ref "C18") (pin "1") (pinfunction "1_1") (pintype "passive"))
      (node (ref "C7") (pin "1") (pinfunction "1_1") (pintype "passive"))
      (node (ref "C8") (pin "1") (pinfunction "1_1") (pintype "passive"))
      (node (ref "D2") (pin "1") (pinfunction "1_1") (pintype "passive"))
      (node (ref "F2") (pin "1") (pinfunction "1_1") (pintype "passive"))
      (node (ref "R22") (pin "1") (pinfunction "1_1") (pintype "passive"))
      (node (ref "U2") (pin "3") (pinfunction "IN_3") (pintype "power_in"))
      (node (ref "U5") (pin "4") (pinfunction "4_4") (pintype "passive"))
      (node (ref "U6") (pin "7") (pinfunction "BAT_7") (pintype "passive"))
    )
    (net (code "55") (name "VBAT_IN") (class "Default")
      (node (ref "F2") (pin "2") (pinfunction "2_2") (pintype "passive"))
      (node (ref "P1") (pin "1") (pinfunction "1_1") (pintype "passive"))
    )
    (net (code "56") (name "unconnected-(J1-H-Pad6)") (class "Default")
      (node (ref "J1") (pin "6") (pinfunction "H_6") (pintype "passive"))
    )
    (net (code "57") (name "unconnected-(J1-H-Pad7)") (class "Default")
      (node (ref "J1") (pin "7") (pinfunction "H_7") (pintype "passive"))
    )
    (net (code "58") (name "unconnected-(J1-H-Pad8)") (class "Default")
      (node (ref "J1") (pin "8") (pinfunction "H_8") (pintype "passive"))
    )
    (net (code "59") (name "unconnected-(J1-H-Pad9)") (class "Default")
      (node (ref "J1") (pin "9") (pinfunction "H_9") (pintype "passive"))
    )
    (net (code "60") (name "unconnected-(U8-PA0-WKUP-Pad10)") (class "Default")
      (node (ref "U8") (pin "10") (pinfunction "PA0-WKUP_10") (pintype "bidirectional"))
    )
    (net (code "61") (name "unconnected-(U8-PA1-Pad11)") (class "Default")
      (node (ref "U8") (pin "11") (pinfunction "PA1_11") (pintype "bidirectional"))
    )
    (net (code "62") (name "unconnected-(U8-PA4-Pad14)") (class "Default")
      (node (ref "U8") (pin "14") (pinfunction "PA4_14") (pintype "bidirectional"))
    )
    (net (code "63") (name "unconnected-(U8-PA5-Pad15)") (class "Default")
      (node (ref "U8") (pin "15") (pinfunction "PA5_15") (pintype "bidirectional"))
    )
    (net (code "64") (name "unconnected-(U8-PA6-Pad16)") (class "Default")
      (node (ref "U8") (pin "16") (pinfunction "PA6_16") (pintype "bidirectional"))
    )
    (net (code "65") (name "unconnected-(U8-PA8-Pad29)") (class "Default")
      (node (ref "U8") (pin "29") (pinfunction "PA8_29") (pintype "bidirectional"))
    )
    (net (code "66") (name "unconnected-(U8-PB3{slash}JTDO-Pad39)") (class "Default")
      (node (ref "U8") (pin "39") (pinfunction "PB3/JTDO_39") (pintype "bidirectional"))
    )
    (net (code "67") (name "unconnected-(U8-PB4{slash}JNTRST-Pad40)") (class "Default")
      (node (ref "U8") (pin "40") (pinfunction "PB4/JNTRST_40") (pintype "bidirectional"))
    )
    (net (code "68") (name "unconnected-(U8-PB9-Pad46)") (class "Default")
      (node (ref "U8") (pin "46") (pinfunction "PB9_46") (pintype "bidirectional"))
    )
    (net (code "69") (name "unconnected-(U8-PB10-Pad21)") (class "Default")
      (node (ref "U8") (pin "21") (pinfunction "PB10_21") (pintype "bidirectional"))
    )
    (net (code "70") (name "unconnected-(U8-PB11-Pad22)") (class "Default")
      (node (ref "U8") (pin "22") (pinfunction "PB11_22") (pintype "bidirectional"))
    )
    (net (code "71") (name "unconnected-(U8-PB12-Pad25)") (class "Default")
      (node (ref "U8") (pin "25") (pinfunction "PB12_25") (pintype "bidirectional"))
    )
    (net (code "72") (name "unconnected-(U8-PB13-Pad26)") (class "Default")
      (node (ref "U8") (pin "26") (pinfunction "PB13_26") (pintype "bidirectional"))
    )
    (net (code "73") (name "unconnected-(U8-PB14-Pad27)") (class "Default")
      (node (ref "U8") (pin "27") (pinfunction "PB14_27") (pintype "bidirectional"))
    )
    (net (code "74") (name "unconnected-(U8-PB15-Pad28)") (class "Default")
      (node (ref "U8") (pin "28") (pinfunction "PB15_28") (pintype "bidirectional"))
    )
    (net (code "75") (name "unconnected-(U8-PC13-TAMPER-RTC-Pad2)") (class "Default")
      (node (ref "U8") (pin "2") (pinfunction "PC13-TAMPER-RTC_2") (pintype "bidirectional"))
    )
    (net (code "76") (name "unconnected-(U8-PC14-OSC32_IN-Pad3)") (class "Default")
      (node (ref "U8") (pin "3") (pinfunction "PC14-OSC32_IN_3") (pintype "bidirectional"))
    )
    (net (code "77") (name "unconnected-(U8-PC15-OSC32_OUT-Pad4)") (class "Default")
      (node (ref "U8") (pin "4") (pinfunction "PC15-OSC32_OUT_4") (pintype "bidirectional"))
    )
  )
)
